# WiFi_Button.net
KiCad netlist of a schematic drawn in EAGLE
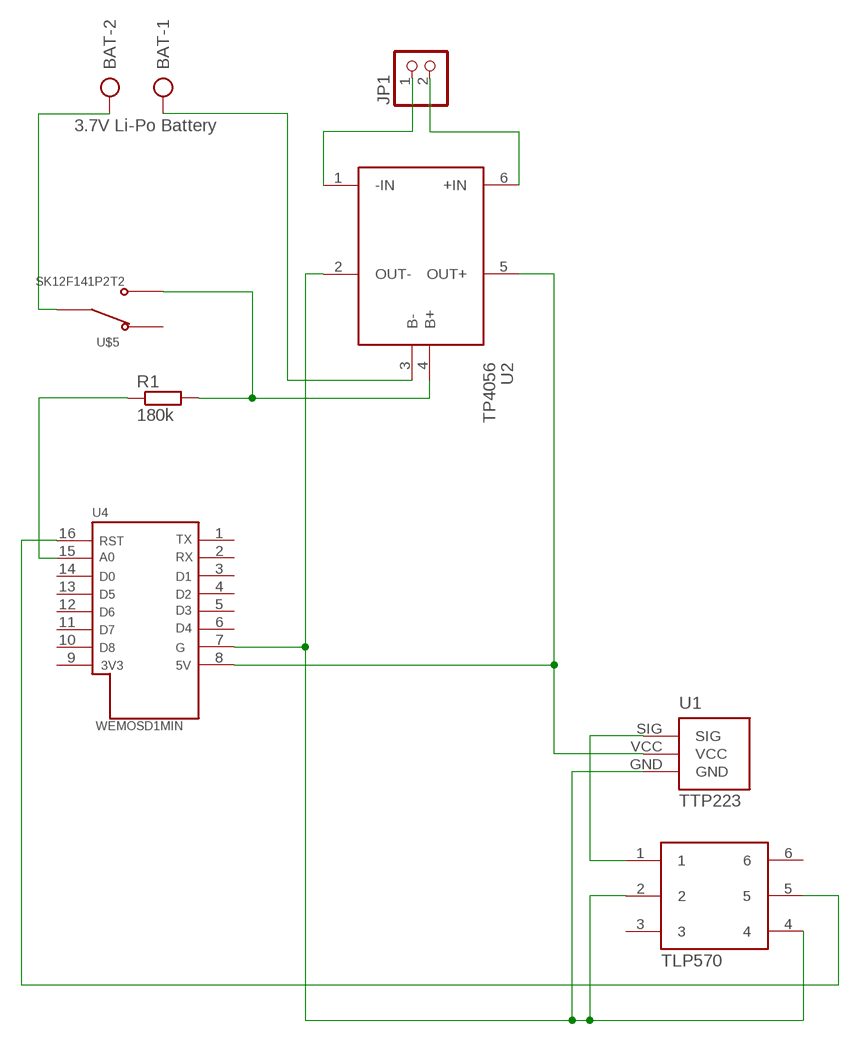
[diagram p0: schematic, sheet 1]

(export (version "E")
  (design (tool "Eeschema 10.0.6"))
  (components
    (comp (ref "BAT")
      (value "AK500/2")
      (footprint "eagle-import:AK500_2")
      (libsource (lib "eagle-import") (part "AK500/2"))
    )
    (comp (ref "JP1")
      (value "PINHD-1X2")
      (footprint "eagle-import:1X02")
      (libsource (lib "eagle-import") (part "PINHD-1X2"))
    )
    (comp (ref "R1")
      (value "180k")
      (footprint "eagle-import:0207_10")
      (libsource (lib "eagle-import") (part "R-EU_0207/10"))
    )
    (comp (ref "U$5")
      (value "SK12F141P2T2")
      (footprint "eagle-import:SK12F141P2T2")
      (libsource (lib "eagle-import") (part "SK12F141P2T2"))
    )
    (comp (ref "U1")
      (value "TTP223")
      (footprint "eagle-import:TTP223")
      (libsource (lib "eagle-import") (part "TTP223"))
    )
    (comp (ref "U2")
      (value "TP4056")
      (footprint "eagle-import:TP4056")
      (libsource (lib "eagle-import") (part "TP4056"))
    )
    (comp (ref "U3")
      (value "TLP570")
      (footprint "eagle-import:DIL06")
      (libsource (lib "eagle-import") (part "TLP570"))
    )
    (comp (ref "U4")
      (value "WEMOSD1MIN")
      (footprint "eagle-import:WEMOSD1MIN")
      (libsource (lib "eagle-import") (part "WEMOSD1MIN"))
    )
  )
  (nets
    (net (code "1") (name "Net-(BATA-KL)") (class "Default")
      (node (ref "BAT") (pin "1") (pinfunction "KL_1") (pintype "passive"))
      (node (ref "U2") (pin "3") (pinfunction "B-_3") (pintype "bidirectional"))
    )
    (net (code "2") (name "Net-(BATB-KL)") (class "Default")
      (node (ref "BAT") (pin "2") (pinfunction "KL_2") (pintype "passive"))
      (node (ref "U$5") (pin "2") (pinfunction "2_2") (pintype "bidirectional"))
    )
    (net (code "3") (name "Net-(U1-PadSIG)") (class "Default")
      (node (ref "U1") (pin "SIG") (pinfunction "SIG_SIG") (pintype "bidirectional"))
      (node (ref "U3") (pin "1") (pinfunction "1_1") (pintype "bidirectional"))
    )
    (net (code "4") (name "Net-(U2-+IN)") (class "Default")
      (node (ref "JP1") (pin "2") (pinfunction "2_2") (pintype "passive"))
      (node (ref "U2") (pin "6") (pinfunction "+IN_6") (pintype "bidirectional"))
    )
    (net (code "5") (name "Net-(U2--IN)") (class "Default")
      (node (ref "JP1") (pin "1") (pinfunction "1_1") (pintype "passive"))
      (node (ref "U2") (pin "1") (pinfunction "-IN_1") (pintype "bidirectional"))
    )
    (net (code "6") (name "Net-(U2-B+)") (class "Default")
      (node (ref "R1") (pin "2") (pinfunction "2_2") (pintype "passive"))
      (node (ref "U$5") (pin "3") (pinfunction "3_3") (pintype "bidirectional"))
      (node (ref "U2") (pin "4") (pinfunction "B+_4") (pintype "bidirectional"))
    )
    (net (code "7") (name "Net-(U2-OUT+)") (class "Default")
      (node (ref "U1") (pin "VCC") (pinfunction "VCC_VCC") (pintype "bidirectional"))
      (node (ref "U2") (pin "5") (pinfunction "OUT+_5") (pintype "bidirectional"))
      (node (ref "U4") (pin "8") (pinfunction "5V_8") (pintype "bidirectional"))
    )
    (net (code "8") (name "Net-(U2-OUT-)") (class "Default")
      (node (ref "U1") (pin "GND") (pinfunction "GND_GND") (pintype "bidirectional"))
      (node (ref "U2") (pin "2") (pinfunction "OUT-_2") (pintype "bidirectional"))
      (node (ref "U3") (pin "2") (pinfunction "2_2") (pintype "bidirectional"))
      (node (ref "U3") (pin "4") (pinfunction "4_4") (pintype "bidirectional"))
      (node (ref "U4") (pin "7") (pinfunction "G_7") (pintype "bidirectional"))
    )
    (net (code "9") (name "Net-(U4-A0)") (class "Default")
      (node (ref "R1") (pin "1") (pinfunction "1_1") (pintype "passive"))
      (node (ref "U4") (pin "15") (pinfunction "A0_15") (pintype "bidirectional"))
    )
    (net (code "10") (name "Net-(U4-RST)") (class "Default")
      (node (ref "U3") (pin "5") (pinfunction "5_5") (pintype "bidirectional"))
      (node (ref "U4") (pin "16") (pinfunction "RST_16") (pintype "bidirectional"))
    )
    (net (code "11") (name "unconnected-(U$5-Pad1)") (class "Default")
      (node (ref "U$5") (pin "1") (pinfunction "1_1") (pintype "bidirectional"))
    )
    (net (code "12") (name "unconnected-(U3-Pad3)") (class "Default")
      (node (ref "U3") (pin "3") (pinfunction "3_3") (pintype "bidirectional"))
    )
    (net (code "13") (name "unconnected-(U3-Pad6)") (class "Default")
      (node (ref "U3") (pin "6") (pinfunction "6_6") (pintype "bidirectional"))
    )
    (net (code "14") (name "unconnected-(U4-3V3-Pad9)") (class "Default")
      (node (ref "U4") (pin "9") (pinfunction "3V3_9") (pintype "bidirectional"))
    )
    (net (code "15") (name "unconnected-(U4-D0-Pad14)") (class "Default")
      (node (ref "U4") (pin "14") (pinfunction "D0_14") (pintype "bidirectional"))
    )
    (net (code "16") (name "unconnected-(U4-D1-Pad3)") (class "Default")
      (node (ref "U4") (pin "3") (pinfunction "D1_3") (pintype "bidirectional"))
    )
    (net (code "17") (name "unconnected-(U4-D2-Pad4)") (class "Default")
      (node (ref "U4") (pin "4") (pinfunction "D2_4") (pintype "bidirectional"))
    )
    (net (code "18") (name "unconnected-(U4-D3-Pad5)") (class "Default")
      (node (ref "U4") (pin "5") (pinfunction "D3_5") (pintype "bidirectional"))
    )
    (net (code "19") (name "unconnected-(U4-D4-Pad6)") (class "Default")
      (node (ref "U4") (pin "6") (pinfunction "D4_6") (pintype "bidirectional"))
    )
    (net (code "20") (name "unconnected-(U4-D5-Pad13)") (class "Default")
      (node (ref "U4") (pin "13") (pinfunction "D5_13") (pintype "bidirectional"))
    )
    (net (code "21") (name "unconnected-(U4-D6-Pad12)") (class "Default")
      (node (ref "U4") (pin "12") (pinfunction "D6_12") (pintype "bidirectional"))
    )
    (net (code "22") (name "unconnected-(U4-D7-Pad11)") (class "Default")
      (node (ref "U4") (pin "11") (pinfunction "D7_11") (pintype "bidirectional"))
    )
    (net (code "23") (name "unconnected-(U4-D8-Pad10)") (class "Default")
      (node (ref "U4") (pin "10") (pinfunction "D8_10") (pintype "bidirectional"))
    )
    (net (code "24") (name "unconnected-(U4-RX-Pad2)") (class "Default")
      (node (ref "U4") (pin "2") (pinfunction "RX_2") (pintype "bidirectional"))
    )
    (net (code "25") (name "unconnected-(U4-TX-Pad1)") (class "Default")
      (node (ref "U4") (pin "1") (pinfunction "TX_1") (pintype "bidirectional"))
    )
  )
)
